# Master_Controller.net
KiCad netlist of a schematic drawn in Altium Designer
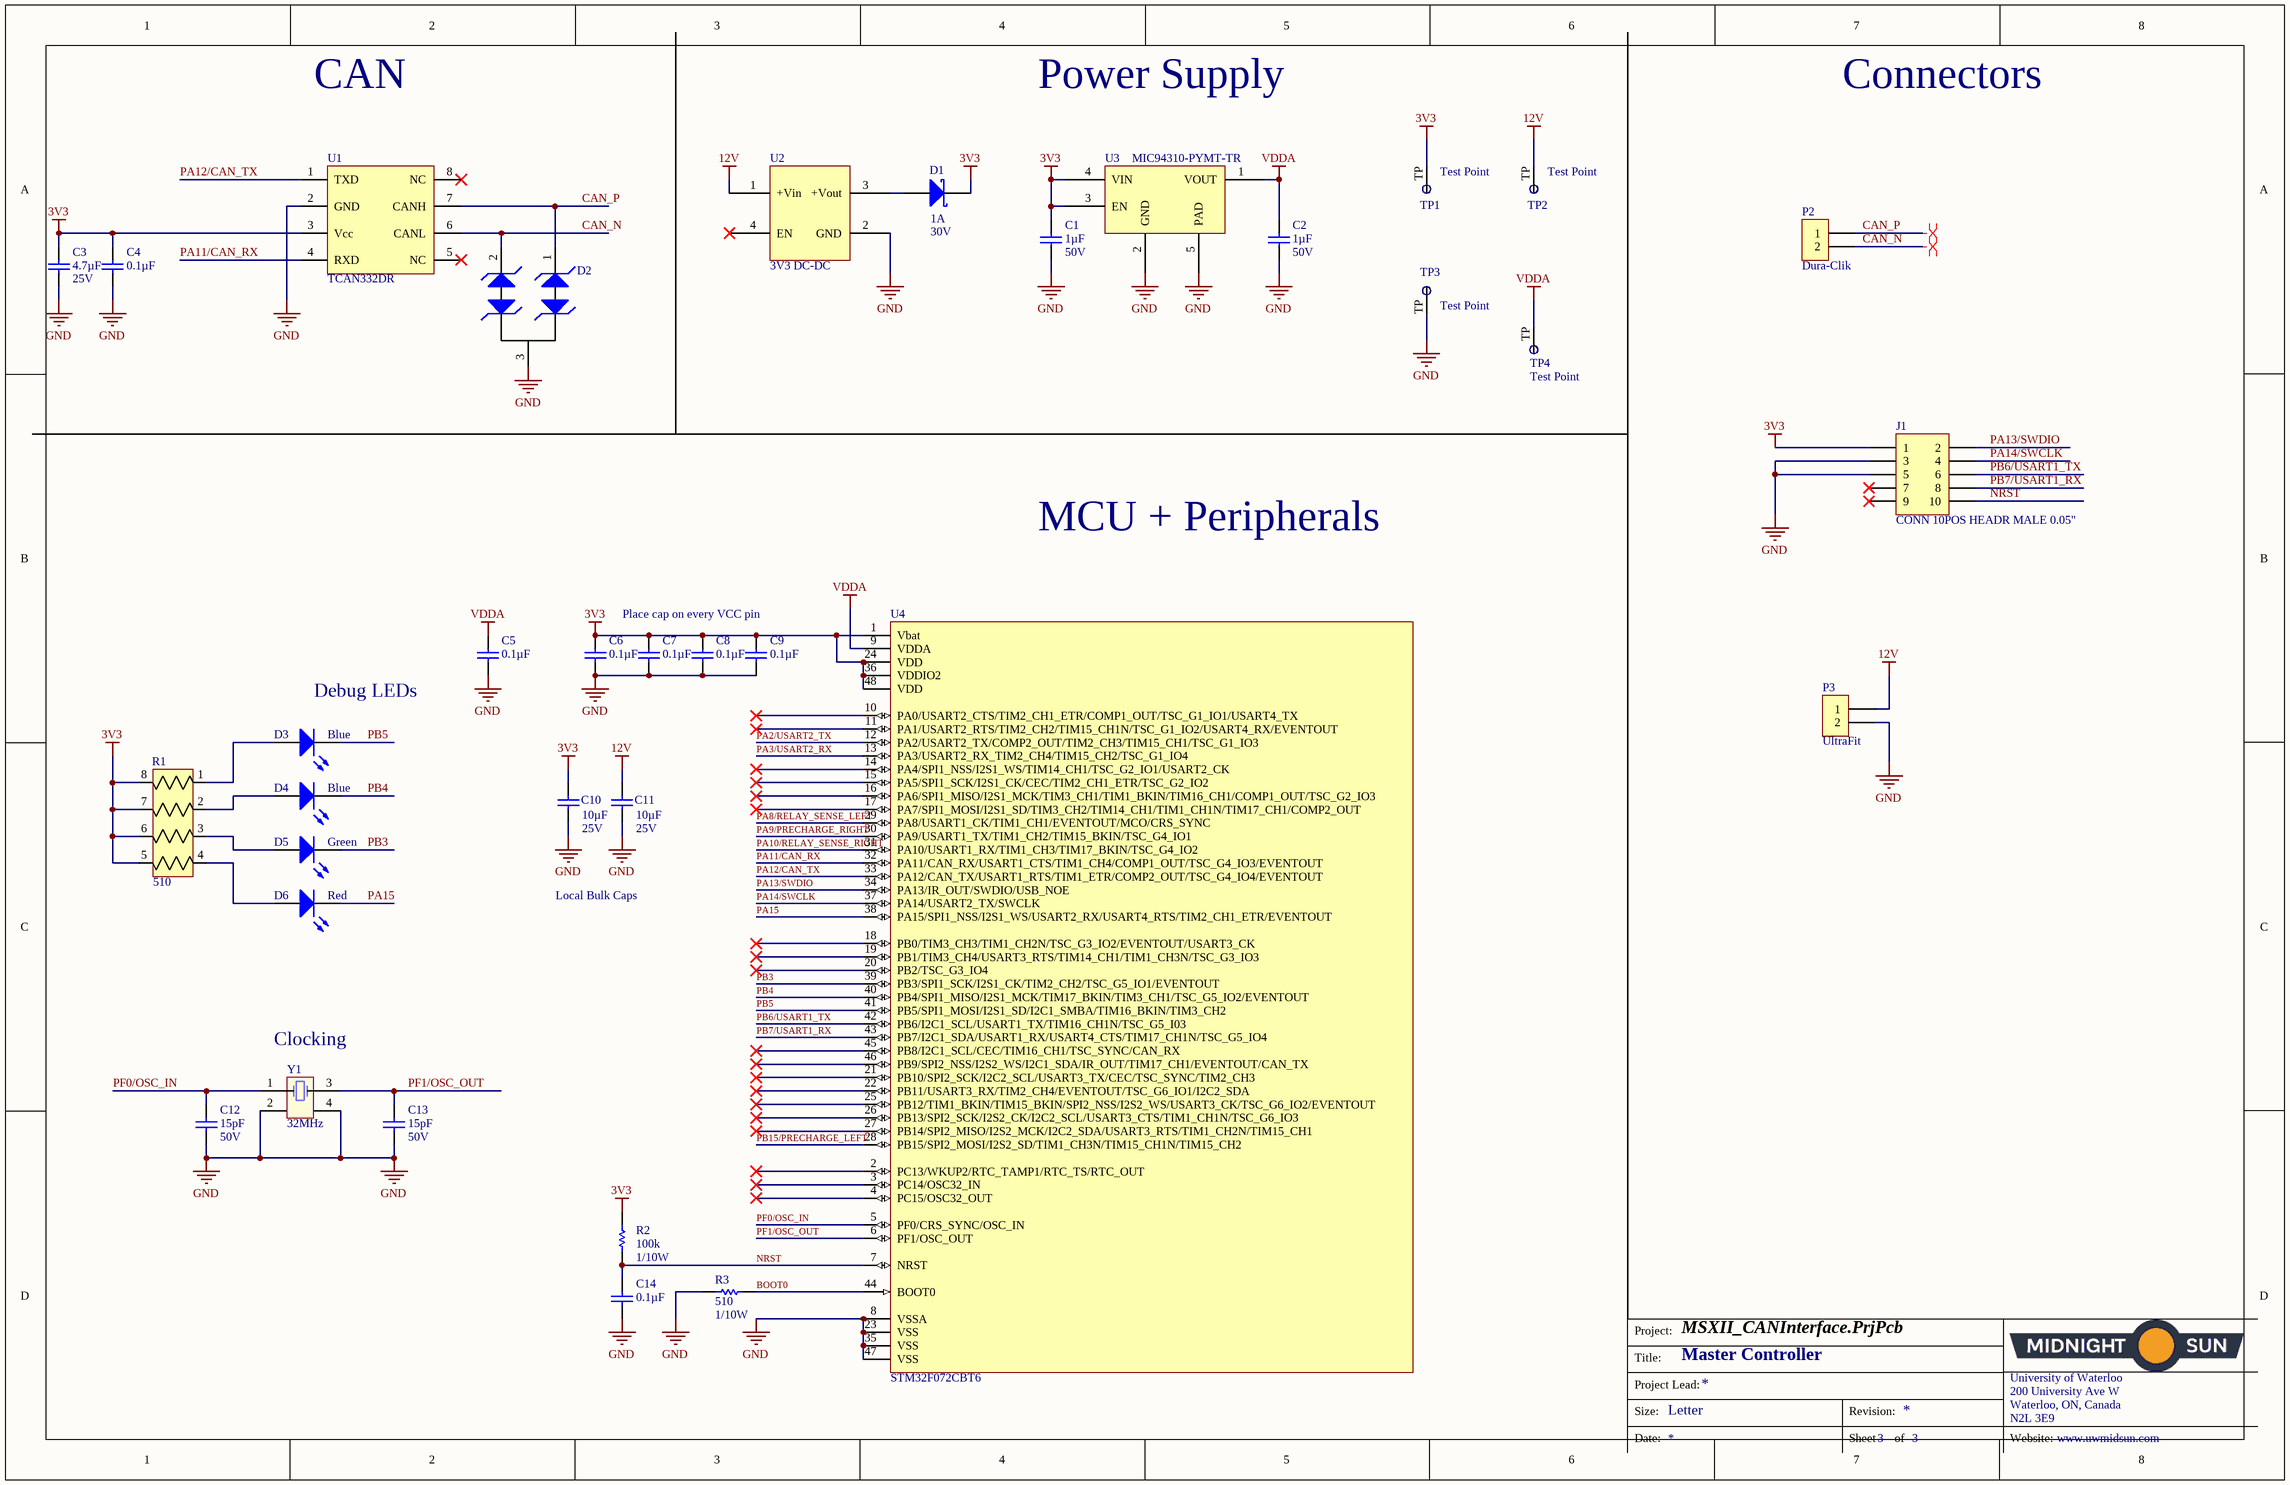
[diagram p0: Master_Controller.SchDoc]

(export (version "E")
  (design (tool "Eeschema 10.0.6"))
  (components
    (comp (ref "C1")
      (value "CAP CER 1UF 50V 10% X7R 0603")
      (footprint "CAP, 0603")
      (description "1µF ±10% 50V Ceramic Capacitor X7R 0603 (1608 Metric)")
      (fields
        (field (name "TOLERANCE") "±10%")
        (field (name "CAPACITANCE") "1µF")
        (field (name "VOLTAGE") "50V")
      )
      (libsource (lib "Schematic Diagrams") (part "CAP CER 1UF 50V 10% X7R 0603"))
    )
    (comp (ref "C2")
      (value "CAP CER 1UF 50V 10% X7R 0603")
      (footprint "CAP, 0603")
      (description "1µF ±10% 50V Ceramic Capacitor X7R 0603 (1608 Metric)")
      (fields
        (field (name "TOLERANCE") "±10%")
        (field (name "CAPACITANCE") "1µF")
        (field (name "VOLTAGE") "50V")
      )
      (libsource (lib "Schematic Diagrams") (part "CAP CER 1UF 50V 10% X7R 0603"))
    )
    (comp (ref "C3")
      (value "CAP CER 4.7UF 25V 10% X5R 0603")
      (footprint "CAP, 0603")
      (description "4.7µF ±10% 25V Ceramic Capacitor X5R 0603 (1608 Metric)")
      (fields
        (field (name "VOLTAGE") "25V")
        (field (name "TOLERANCE") "±10%")
        (field (name "CAPACITANCE") "4.7µF")
      )
      (libsource (lib "Schematic Diagrams") (part "CAP CER 4.7UF 25V 10% X5R 0603"))
    )
    (comp (ref "C4")
      (value "CAP CER 0.1UF 50V 10% X7R 0603")
      (footprint "CAP, 0603")
      (description "0.10µF ±10% 50V Ceramic Capacitor X7R 0603 (1608 Metric)")
      (fields
        (field (name "VOLTAGE") "50V")
        (field (name "TOLERANCE") "±10%")
        (field (name "CAPACITANCE") "0.1µF")
      )
      (libsource (lib "Schematic Diagrams") (part "CAP CER 0.1UF 50V 10% X7R 0603"))
    )
    (comp (ref "C5")
      (value "CAP CER 0.1UF 50V 10% X7R 0603")
      (footprint "CAP, 0603")
      (description "0.10µF ±10% 50V Ceramic Capacitor X7R 0603 (1608 Metric)")
      (fields
        (field (name "VOLTAGE") "50V")
        (field (name "TOLERANCE") "±10%")
        (field (name "CAPACITANCE") "0.1µF")
      )
      (libsource (lib "Schematic Diagrams") (part "CAP CER 0.1UF 50V 10% X7R 0603"))
    )
    (comp (ref "C6")
      (value "CAP CER 0.1UF 50V 10% X7R 0603")
      (footprint "CAP, 0603")
      (description "0.10µF ±10% 50V Ceramic Capacitor X7R 0603 (1608 Metric)")
      (fields
        (field (name "VOLTAGE") "50V")
        (field (name "TOLERANCE") "±10%")
        (field (name "CAPACITANCE") "0.1µF")
      )
      (libsource (lib "Schematic Diagrams") (part "CAP CER 0.1UF 50V 10% X7R 0603"))
    )
    (comp (ref "C7")
      (value "CAP CER 0.1UF 50V 10% X7R 0603")
      (footprint "CAP, 0603")
      (description "0.10µF ±10% 50V Ceramic Capacitor X7R 0603 (1608 Metric)")
      (fields
        (field (name "VOLTAGE") "50V")
        (field (name "TOLERANCE") "±10%")
        (field (name "CAPACITANCE") "0.1µF")
      )
      (libsource (lib "Schematic Diagrams") (part "CAP CER 0.1UF 50V 10% X7R 0603"))
    )
    (comp (ref "C8")
      (value "CAP CER 0.1UF 50V 10% X7R 0603")
      (footprint "CAP, 0603")
      (description "0.10µF ±10% 50V Ceramic Capacitor X7R 0603 (1608 Metric)")
      (fields
        (field (name "VOLTAGE") "50V")
        (field (name "TOLERANCE") "±10%")
        (field (name "CAPACITANCE") "0.1µF")
      )
      (libsource (lib "Schematic Diagrams") (part "CAP CER 0.1UF 50V 10% X7R 0603"))
    )
    (comp (ref "C9")
      (value "CAP CER 0.1UF 50V 10% X7R 0603")
      (footprint "CAP, 0603")
      (description "0.10µF ±10% 50V Ceramic Capacitor X7R 0603 (1608 Metric)")
      (fields
        (field (name "VOLTAGE") "50V")
        (field (name "TOLERANCE") "±10%")
        (field (name "CAPACITANCE") "0.1µF")
      )
      (libsource (lib "Schematic Diagrams") (part "CAP CER 0.1UF 50V 10% X7R 0603"))
    )
    (comp (ref "C10")
      (value "CAP CER 10uF 25V 10% X5R 0805")
      (footprint "CAP, 0805")
      (description "10µF ±10% 25V Ceramic Capacitor X5R 0805 (2012 Metric)")
      (fields
        (field (name "MANUFACTURER") "Murata Electronics North America")
        (field (name "MANUFACTURER PART NUMBER") "GRM21BR61E106KA73L")
        (field (name "VOLTAGE - RATED") "25V")
        (field (name "CAPACITANCE") "10µF")
      )
      (libsource (lib "Schematic Diagrams") (part "CAP CER 10uF 25V 10% X5R 0805"))
    )
    (comp (ref "C11")
      (value "CAP CER 10uF 25V 10% X5R 0805")
      (footprint "CAP, 0805")
      (description "10µF ±10% 25V Ceramic Capacitor X5R 0805 (2012 Metric)")
      (fields
        (field (name "MANUFACTURER") "Murata Electronics North America")
        (field (name "MANUFACTURER PART NUMBER") "GRM21BR61E106KA73L")
        (field (name "VOLTAGE - RATED") "25V")
        (field (name "CAPACITANCE") "10µF")
      )
      (libsource (lib "Schematic Diagrams") (part "CAP CER 10uF 25V 10% X5R 0805"))
    )
    (comp (ref "C12")
      (value "CAP CER 15PF 50V ±5% NPO 0603")
      (footprint "CAP, 0603")
      (description "15pF ±5% 50V Ceramic Capacitor C0G, NP0 0603 (1608 Metric)")
      (fields
        (field (name "VOLTAGE") "50V")
        (field (name "TOLERANCE") "±5%")
        (field (name "CAPACITANCE") "15pF")
      )
      (libsource (lib "Schematic Diagrams") (part "CAP CER 15PF 50V ±5% NPO 0603"))
    )
    (comp (ref "C13")
      (value "CAP CER 15PF 50V ±5% NPO 0603")
      (footprint "CAP, 0603")
      (description "15pF ±5% 50V Ceramic Capacitor C0G, NP0 0603 (1608 Metric)")
      (fields
        (field (name "VOLTAGE") "50V")
        (field (name "TOLERANCE") "±5%")
        (field (name "CAPACITANCE") "15pF")
      )
      (libsource (lib "Schematic Diagrams") (part "CAP CER 15PF 50V ±5% NPO 0603"))
    )
    (comp (ref "C14")
      (value "CAP CER 0.1UF 50V 10% X7R 0603")
      (footprint "CAP, 0603")
      (description "0.10µF ±10% 50V Ceramic Capacitor X7R 0603 (1608 Metric)")
      (fields
        (field (name "VOLTAGE") "50V")
        (field (name "TOLERANCE") "±10%")
        (field (name "CAPACITANCE") "0.1µF")
      )
      (libsource (lib "Schematic Diagrams") (part "CAP CER 0.1UF 50V 10% X7R 0603"))
    )
    (comp (ref "D1")
      (value "DIODE SCHOTTKY 30V 1A POWERDI123")
      (footprint "DIODE SCHOTTKY 30V 1A POWERDI123")
      (description "Diode Schottky 30V 1A Surface Mount PowerDI™ 123")
      (fields
        (field (name "MANUFACTURER") "Diodes Incorporated")
        (field (name "MANUFACTURER PART NUMBER") "DFLS130L-7")
        (field (name "CURRENT - AVERAGE RECTIFIED (IO)") "1A")
        (field (name "VOLTAGE - DC REVERSE (VR) (MAX)") "30V")
      )
      (libsource (lib "Schematic Diagrams") (part "DIODE SCHOTTKY 30V 1A POWERDI123"))
    )
    (comp (ref "D2")
      (value "DIODE TVS 24VWM 70VC SOT23")
      (footprint "SOT23")
      (description "TVS DIODE 24VWM 70VC SOT23")
      (libsource (lib "Schematic Diagrams") (part "DIODE TVS 24VWM 70VC SOT23"))
    )
    (comp (ref "D3")
      (value "LED BLUE CLEAR 2.8V 0603")
      (footprint "LED_0603")
      (description "Blue 470nm LED Indication - Discrete 2.8V 0603 (1608 Metric)")
      (fields (field (name "COLOR") "Blue"))
      (libsource (lib "Schematic Diagrams") (part "LED BLUE CLEAR 2.8V 0603"))
    )
    (comp (ref "D4")
      (value "LED BLUE CLEAR 2.8V 0603")
      (footprint "LED_0603")
      (description "Blue 470nm LED Indication - Discrete 2.8V 0603 (1608 Metric)")
      (fields (field (name "COLOR") "Blue"))
      (libsource (lib "Schematic Diagrams") (part "LED BLUE CLEAR 2.8V 0603"))
    )
    (comp (ref "D5")
      (value "LED GREEN CLEAR 2V 0603")
      (footprint "LED_0603")
      (description "Green 572nm LED Indication - Discrete 2V 0603 (1608 Metric)")
      (fields
        (field (name "COLOR") "Green")
        (field (name "MANUFACTURER") "Wurth Electronics Inc.")
        (field (name "MANUFACTURER PART NUMBER") "150060VS75000")
      )
      (libsource (lib "Schematic Diagrams") (part "LED GREEN CLEAR 2V 0603"))
    )
    (comp (ref "D6")
      (value "LED RED CLEAR 2V 0603")
      (footprint "LED_0603")
      (description "Red 631nm LED Indication - Discrete 2V 0603 (1608 Metric)")
      (fields
        (field (name "COLOR") "Red")
        (field (name "MANUFACTURER") "Wurth Electronics Inc.")
        (field (name "MANUFACTURER PART NUMBER") "150060RS75000")
      )
      (libsource (lib "Schematic Diagrams") (part "LED RED CLEAR 2V 0603"))
    )
    (comp (ref "J1")
      (value "CONN 10POS HEADR MALE 0.05\"")
      (footprint "CONN, 10POS 0.05\" Debug Header")
      (description "10 Positions Header Connector 0.050\" (1.27mm) Surface Mount Gold")
      (libsource (lib "Schematic Diagrams") (part "CONN 10POS HEADR MALE 0.05{dblquote}"))
    )
    (comp (ref "P2")
      (value "Dura-Clik")
      (footprint "CONN, 2POS Dura-Click Vertical")
      (description "2 Positions Header, Shrouded Connector 0.079\" (2.00mm) Surface Mount, Vertical Tin")
      (fields
        (field (name "MANUFACTURER") "Molex, LLC")
        (field (name "MANUFACTURER PART NUMBER") "5600200220")
      )
      (libsource (lib "Schematic Diagrams") (part "CONN 2POS DURA-CLIK 0.079{dblquote} VERT"))
    )
    (comp (ref "P3")
      (value "CONN 2POS ULTRA-FIT 0.138\"")
      (footprint "CONN, 2POS ULTRA-FIT")
      (description "2 Positions Header, Shrouded Connector 0.138\" (3.50mm) Through Hole Gold")
      (fields (field (name "VOLTAGE") "400V") (field (name "SERIES") "UltraFit"))
      (libsource (lib "Schematic Diagrams") (part "CONN 2POS ULTRA-FIT 0.138{dblquote}"))
    )
    (comp (ref "R1")
      (value "RES ARRAY 510 OHM 5% 4RES")
      (footprint "RES ARRAY 4 POS 0804")
      (description "RES ARRAY SMD 510 OHM 5% 4RES EXB-N8V511JX")
      (fields
        (field (name "MANUFACTURER") "Panasonic Electronic Components")
        (field (name "MANUFACTURER PART NUMBER") "EXB-N8V511JX")
        (field (name "RESISTANCE (OHMS)") "510")
      )
      (libsource (lib "Schematic Diagrams") (part "RES ARRAY 510 OHM 5% 4RES EXB-N8V511JX"))
    )
    (comp (ref "R2")
      (value "RES 100K OHM 5% 1/8W 0603")
      (footprint "RES, 0603")
      (description "RES SMD 100K OHM 5% 1/10W 0603")
      (fields
        (field (name "TOLERANCE") "±5%")
        (field (name "RESISTANCE") "100k")
        (field (name "POWER") "1/10W")
      )
      (libsource (lib "Schematic Diagrams") (part "RES 100K OHM 5% 1/8W 0603"))
    )
    (comp (ref "R3")
      (value "RES 510 OHM 5% 1/10W 0603")
      (footprint "RES, 0603")
      (description "RES SMD 510 OHM 5% 1/10W 0603")
      (fields
        (field (name "TOLERANCE") "±5%")
        (field (name "RESISTANCE") "510")
        (field (name "POWER") "1/10W")
      )
      (libsource (lib "Schematic Diagrams") (part "RES 510 OHM 5% 1/10W 0603"))
    )
    (comp (ref "TP1")
      (value "Test Point")
      (footprint "Test Point")
      (libsource (lib "Schematic Diagrams") (part "Test Point"))
    )
    (comp (ref "TP2")
      (value "Test Point")
      (footprint "Test Point")
      (libsource (lib "Schematic Diagrams") (part "Test Point"))
    )
    (comp (ref "TP3")
      (value "Test Point")
      (footprint "Test Point")
      (libsource (lib "Schematic Diagrams") (part "Test Point"))
    )
    (comp (ref "TP4")
      (value "Test Point")
      (footprint "Test Point")
      (libsource (lib "Schematic Diagrams") (part "Test Point"))
    )
    (comp (ref "U1")
      (value "IC CAN Tranceiver TCAN332DR")
      (footprint "TSOP65P280X145-8N")
      (description "1/1 Transceiver CAN 8-SOIC")
      (fields
        (field (name "MANUFACTURER PART NUMBER") "TCAN332DR")
        (field (name "DIGIKEY PART NUMBER") "296-43711-1-ND")
      )
      (libsource (lib "Schematic Diagrams") (part "IC CAN Tranceiver TCAN332DR"))
    )
    (comp (ref "U2")
      (value "IC DCDC 3.3V 0.5A 4-SMD")
      (footprint "IC DCDC 3.3V 0.5A 4-SMD")
      (description "Non-isolated PoL DC-DC Module 3.3V Output 0.5A 5-36V Input")
      (fields
        (field (name "MANUFACTURER") "Recom Power")
        (field (name "MANUFACTURER PART NUMBER") "ROF-78E3.3-0.5SMD-R")
      )
      (libsource (lib "Schematic Diagrams") (part "IC DCDC 3.3V 0.5A 4-SMD"))
    )
    (comp (ref "U3")
      (value "IC REG LDO 3V 0.2A 4-TDFN")
      (footprint "IC REG LDO 3V 0.2A 4-TDFN")
      (fields
        (field (name "MANUFACTURER") "Microchip Technology")
        (field (name "MANUFACTURER PART NUMBER") "MIC94310-PYMT-TR")
      )
      (libsource (lib "Schematic Diagrams") (part "IC REG LDO 3V 0.2A 4-TDFN"))
    )
    (comp (ref "U4")
      (value "IC MCU 32BIT 128KB FLASH 48LQFP")
      (footprint "TSQFP50P890X890X160-48M")
      (description "ARM® Cortex®-M0 STM32 F0 Microcontroller IC 32-Bit 48MHz 128KB (128K x 8) FLASH 48-LQFP (7x7)")
      (fields (field (name "MANUFACTURER PART NUMBER 1") "STM32F072CBT6"))
      (libsource (lib "Schematic Diagrams") (part "IC MCU 32BIT 128KB FLASH 48LQFP"))
    )
    (comp (ref "Y1")
      (value "CRYSTAL 32 MHz 8pF 4-SMD")
      (footprint "CX2520DB CRYSTAL")
      (description "32MHz ±15ppm Crystal 8pF 50 Ohm -40°C ~ 85°C AEC-Q200 Surface Mount 4-SMD, No Lead")
      (fields (field (name "FREQUENCY") "32MHz"))
      (libsource (lib "Schematic Diagrams") (part "CRYSTAL 32 MHz 8pF 4-SMD"))
    )
  )
  (nets
    (net (code "1") (name "/BOOT0") (class "Default")
      (node (ref "R3") (pin "2") (pinfunction "2_2") (pintype "passive"))
      (node (ref "U4") (pin "44") (pinfunction "BOOT0_44") (pintype "input"))
    )
    (net (code "2") (name "/CAN_N") (class "Default")
      (node (ref "D2") (pin "2") (pinfunction "Cathode2_2") (pintype "passive"))
      (node (ref "P2") (pin "2") (pinfunction "2_2") (pintype "passive"))
      (node (ref "U1") (pin "6") (pinfunction "CANL_6") (pintype "passive"))
    )
    (net (code "3") (name "/CAN_P") (class "Default")
      (node (ref "D2") (pin "1") (pinfunction "Cathode1_1") (pintype "passive"))
      (node (ref "P2") (pin "1") (pinfunction "1_1") (pintype "passive"))
      (node (ref "U1") (pin "7") (pinfunction "CANH_7") (pintype "passive"))
    )
    (net (code "4") (name "/NRST") (class "Default")
      (node (ref "C14") (pin "2") (pinfunction "2_2") (pintype "passive"))
      (node (ref "J1") (pin "10") (pinfunction "10_10") (pintype "passive"))
      (node (ref "R2") (pin "1") (pinfunction "1_1") (pintype "passive"))
      (node (ref "U4") (pin "7") (pinfunction "NRST_7") (pintype "bidirectional"))
    )
    (net (code "5") (name "/PA2{slash}USART2_TX") (class "Default")
      (node (ref "U4") (pin "12") (pinfunction "PA2/USART2_TX/COMP2_OUT/TIM2_CH3/TIM15_CH1/TSC_G1_IO3_12") (pintype "bidirectional"))
    )
    (net (code "6") (name "/PA3{slash}USART2_RX") (class "Default")
      (node (ref "U4") (pin "13") (pinfunction "PA3/USART2_RX_TIM2_CH4/TIM15_CH2/TSC_G1_IO4_13") (pintype "bidirectional"))
    )
    (net (code "7") (name "/PA8{slash}RELAY_SENSE_LEFT") (class "Default")
      (node (ref "U4") (pin "29") (pinfunction "PA8/USART1_CK/TIM1_CH1/EVENTOUT/MCO/CRS_SYNC_29") (pintype "bidirectional"))
    )
    (net (code "8") (name "/PA9{slash}PRECHARGE_RIGHT") (class "Default")
      (node (ref "U4") (pin "30") (pinfunction "PA9/USART1_TX/TIM1_CH2/TIM15_BKIN/TSC_G4_IO1_30") (pintype "bidirectional"))
    )
    (net (code "9") (name "/PA10{slash}RELAY_SENSE_RIGHT") (class "Default")
      (node (ref "U4") (pin "31") (pinfunction "PA10/USART1_RX/TIM1_CH3/TIM17_BKIN/TSC_G4_IO2_31") (pintype "bidirectional"))
    )
    (net (code "10") (name "/PA11{slash}CAN_RX") (class "Default")
      (node (ref "U1") (pin "4") (pinfunction "RXD_4") (pintype "passive"))
      (node (ref "U4") (pin "32") (pinfunction "PA11/CAN_RX/USART1_CTS/TIM1_CH4/COMP1_OUT/TSC_G4_IO3/EVENTOUT_32") (pintype "bidirectional"))
    )
    (net (code "11") (name "/PA12{slash}CAN_TX") (class "Default")
      (node (ref "U1") (pin "1") (pinfunction "TXD_1") (pintype "passive"))
      (node (ref "U4") (pin "33") (pinfunction "PA12/CAN_TX/USART1_RTS/TIM1_ETR/COMP2_OUT/TSC_G4_IO4/EVENTOUT_33") (pintype "bidirectional"))
    )
    (net (code "12") (name "/PA13{slash}SWDIO") (class "Default")
      (node (ref "J1") (pin "2") (pinfunction "2_2") (pintype "passive"))
      (node (ref "U4") (pin "34") (pinfunction "PA13/IR_OUT/SWDIO/USB_NOE_34") (pintype "bidirectional"))
    )
    (net (code "13") (name "/PA14{slash}SWCLK") (class "Default")
      (node (ref "J1") (pin "4") (pinfunction "4_4") (pintype "passive"))
      (node (ref "U4") (pin "37") (pinfunction "PA14/USART2_TX/SWCLK_37") (pintype "bidirectional"))
    )
    (net (code "14") (name "/PA15") (class "Default")
      (node (ref "D6") (pin "2") (pinfunction "K_2") (pintype "passive"))
      (node (ref "U4") (pin "38") (pinfunction "PA15/SPI1_NSS/I2S1_WS/USART2_RX/USART4_RTS/TIM2_CH1_ETR/EVENTOUT_38") (pintype "bidirectional"))
    )
    (net (code "15") (name "/PB3") (class "Default")
      (node (ref "D5") (pin "2") (pinfunction "K_2") (pintype "passive"))
      (node (ref "U4") (pin "39") (pinfunction "PB3/SPI1_SCK/I2S1_CK/TIM2_CH2/TSC_G5_IO1/EVENTOUT_39") (pintype "bidirectional"))
    )
    (net (code "16") (name "/PB4") (class "Default")
      (node (ref "D4") (pin "2") (pinfunction "K_2") (pintype "passive"))
      (node (ref "U4") (pin "40") (pinfunction "PB4/SPI1_MISO/I2S1_MCK/TIM17_BKIN/TIM3_CH1/TSC_G5_IO2/EVENTOUT_40") (pintype "bidirectional"))
    )
    (net (code "17") (name "/PB5") (class "Default")
      (node (ref "D3") (pin "2") (pinfunction "K_2") (pintype "passive"))
      (node (ref "U4") (pin "41") (pinfunction "PB5/SPI1_MOSI/I2S1_SD/I2C1_SMBA/TIM16_BKIN/TIM3_CH2_41") (pintype "bidirectional"))
    )
    (net (code "18") (name "/PB6{slash}USART1_TX") (class "Default")
      (node (ref "J1") (pin "6") (pinfunction "6_6") (pintype "passive"))
      (node (ref "U4") (pin "42") (pinfunction "PB6/I2C1_SCL/USART1_TX/TIM16_CH1N/TSC_G5_I03_42") (pintype "bidirectional"))
    )
    (net (code "19") (name "/PB7{slash}USART1_RX") (class "Default")
      (node (ref "J1") (pin "8") (pinfunction "8_8") (pintype "passive"))
      (node (ref "U4") (pin "43") (pinfunction "PB7/I2C1_SDA/USART1_RX/USART4_CTS/TIM17_CH1N/TSC_G5_IO4_43") (pintype "bidirectional"))
    )
    (net (code "20") (name "/PB15{slash}PRECHARGE_LEFT") (class "Default")
      (node (ref "U4") (pin "28") (pinfunction "PB15/SPI2_MOSI/I2S2_SD/TIM1_CH3N/TIM15_CH1N/TIM15_CH2_28") (pintype "bidirectional"))
    )
    (net (code "21") (name "/PF0{slash}OSC_IN") (class "Default")
      (node (ref "C12") (pin "2") (pinfunction "2_2") (pintype "passive"))
      (node (ref "U4") (pin "5") (pinfunction "PF0/CRS_SYNC/OSC_IN_5") (pintype "bidirectional"))
      (node (ref "Y1") (pin "1") (pinfunction "OSC1_1") (pintype "passive"))
    )
    (net (code "22") (name "/PF1{slash}OSC_OUT") (class "Default")
      (node (ref "C13") (pin "2") (pinfunction "2_2") (pintype "passive"))
      (node (ref "U4") (pin "6") (pinfunction "PF1/OSC_OUT_6") (pintype "bidirectional"))
      (node (ref "Y1") (pin "3") (pinfunction "OSC2_3") (pintype "passive"))
    )
    (net (code "23") (name "3V3") (class "Default")
      (node (ref "C1") (pin "1") (pinfunction "1_1") (pintype "passive"))
      (node (ref "C10") (pin "1") (pinfunction "1_1") (pintype "passive"))
      (node (ref "C3") (pin "2") (pinfunction "2_2") (pintype "passive"))
      (node (ref "C4") (pin "2") (pinfunction "2_2") (pintype "passive"))
      (node (ref "C6") (pin "2") (pinfunction "2_2") (pintype "passive"))
      (node (ref "C7") (pin "2") (pinfunction "2_2") (pintype "passive"))
      (node (ref "C8") (pin "2") (pinfunction "2_2") (pintype "passive"))
      (node (ref "C9") (pin "2") (pinfunction "2_2") (pintype "passive"))
      (node (ref "D1") (pin "2") (pinfunction "K_2") (pintype "passive"))
      (node (ref "J1") (pin "1") (pinfunction "1_1") (pintype "passive"))
      (node (ref "R1") (pin "5") (pinfunction "5_5") (pintype "passive"))
      (node (ref "R1") (pin "6") (pinfunction "6_6") (pintype "passive"))
      (node (ref "R1") (pin "7") (pinfunction "7_7") (pintype "passive"))
      (node (ref "R1") (pin "8") (pinfunction "8_8") (pintype "passive"))
      (node (ref "R2") (pin "2") (pinfunction "2_2") (pintype "passive"))
      (node (ref "TP1") (pin "TP") (pinfunction "1_TP") (pintype "passive"))
      (node (ref "U1") (pin "3") (pinfunction "Vcc_3") (pintype "passive"))
      (node (ref "U3") (pin "3") (pinfunction "EN_3") (pintype "passive"))
      (node (ref "U3") (pin "4") (pinfunction "VIN_4") (pintype "passive"))
      (node (ref "U4") (pin "1") (pinfunction "Vbat_1") (pintype "power_in"))
      (node (ref "U4") (pin "24") (pinfunction "VDD_24") (pintype "power_in"))
      (node (ref "U4") (pin "36") (pinfunction "VDDIO2_36") (pintype "power_in"))
      (node (ref "U4") (pin "48") (pinfunction "VDD_48") (pintype "power_in"))
    )
    (net (code "24") (name "12V") (class "Default")
      (node (ref "C11") (pin "1") (pinfunction "1_1") (pintype "passive"))
      (node (ref "P3") (pin "1") (pinfunction "1_1") (pintype "passive"))
      (node (ref "TP2") (pin "TP") (pinfunction "1_TP") (pintype "passive"))
      (node (ref "U2") (pin "1") (pinfunction "+Vin_1") (pintype "passive"))
    )
    (net (code "25") (name "GND") (class "Default")
      (node (ref "C1") (pin "2") (pinfunction "2_2") (pintype "passive"))
      (node (ref "C10") (pin "2") (pinfunction "2_2") (pintype "passive"))
      (node (ref "C11") (pin "2") (pinfunction "2_2") (pintype "passive"))
      (node (ref "C12") (pin "1") (pinfunction "1_1") (pintype "passive"))
      (node (ref "C13") (pin "1") (pinfunction "1_1") (pintype "passive"))
      (node (ref "C14") (pin "1") (pinfunction "1_1") (pintype "passive"))
      (node (ref "C2") (pin "2") (pinfunction "2_2") (pintype "passive"))
      (node (ref "C3") (pin "1") (pinfunction "1_1") (pintype "passive"))
      (node (ref "C4") (pin "1") (pinfunction "1_1") (pintype "passive"))
      (node (ref "C5") (pin "1") (pinfunction "1_1") (pintype "passive"))
      (node (ref "C6") (pin "1") (pinfunction "1_1") (pintype "passive"))
      (node (ref "C7") (pin "1") (pinfunction "1_1") (pintype "passive"))
      (node (ref "C8") (pin "1") (pinfunction "1_1") (pintype "passive"))
      (node (ref "C9") (pin "1") (pinfunction "1_1") (pintype "passive"))
      (node (ref "D2") (pin "3") (pinfunction "Common_Cathode_3") (pintype "power_in"))
      (node (ref "J1") (pin "3") (pinfunction "3_3") (pintype "passive"))
      (node (ref "J1") (pin "5") (pinfunction "5_5") (pintype "passive"))
      (node (ref "P3") (pin "2") (pinfunction "2_2") (pintype "passive"))
      (node (ref "R3") (pin "1") (pinfunction "1_1") (pintype "passive"))
      (node (ref "TP3") (pin "TP") (pinfunction "1_TP") (pintype "passive"))
      (node (ref "U1") (pin "2") (pinfunction "GND_2") (pintype "passive"))
      (node (ref "U2") (pin "2") (pinfunction "GND_2") (pintype "passive"))
      (node (ref "U3") (pin "2") (pinfunction "GND_2") (pintype "passive"))
      (node (ref "U3") (pin "5") (pinfunction "PAD_5") (pintype "passive"))
      (node (ref "U4") (pin "23") (pinfunction "VSS_23") (pintype "power_in"))
      (node (ref "U4") (pin "35") (pinfunction "VSS_35") (pintype "power_in"))
      (node (ref "U4") (pin "47") (pinfunction "VSS_47") (pintype "power_in"))
      (node (ref "U4") (pin "8") (pinfunction "VSSA_8") (pintype "power_in"))
      (node (ref "Y1") (pin "2") (pinfunction "2_2") (pintype "passive"))
      (node (ref "Y1") (pin "4") (pinfunction "3_4") (pintype "passive"))
    )
    (net (code "26") (name "Net-(D1-A)") (class "Default")
      (node (ref "D1") (pin "1") (pinfunction "A_1") (pintype "passive"))
      (node (ref "U2") (pin "3") (pinfunction "+Vout_3") (pintype "passive"))
    )
    (net (code "27") (name "Net-(D3-A)") (class "Default")
      (node (ref "D3") (pin "1") (pinfunction "A_1") (pintype "passive"))
      (node (ref "R1") (pin "1") (pinfunction "1_1") (pintype "passive"))
    )
    (net (code "28") (name "Net-(D4-A)") (class "Default")
      (node (ref "D4") (pin "1") (pinfunction "A_1") (pintype "passive"))
      (node (ref "R1") (pin "2") (pinfunction "2_2") (pintype "passive"))
    )
    (net (code "29") (name "Net-(D5-A)") (class "Default")
      (node (ref "D5") (pin "1") (pinfunction "A_1") (pintype "passive"))
      (node (ref "R1") (pin "3") (pinfunction "3_3") (pintype "passive"))
    )
    (net (code "30") (name "Net-(D6-A)") (class "Default")
      (node (ref "D6") (pin "1") (pinfunction "A_1") (pintype "passive"))
      (node (ref "R1") (pin "4") (pinfunction "4_4") (pintype "passive"))
    )
    (net (code "31") (name "VDDA") (class "Default")
      (node (ref "C2") (pin "1") (pinfunction "1_1") (pintype "passive"))
      (node (ref "C5") (pin "2") (pinfunction "2_2") (pintype "passive"))
      (node (ref "TP4") (pin "TP") (pinfunction "1_TP") (pintype "passive"))
      (node (ref "U3") (pin "1") (pinfunction "VOUT_1") (pintype "passive"))
      (node (ref "U4") (pin "9") (pinfunction "VDDA_9") (pintype "power_in"))
    )
    (net (code "32") (name "unconnected-(J1-Pad7)") (class "Default")
      (node (ref "J1") (pin "7") (pinfunction "7_7") (pintype "passive+no_connect"))
    )
    (net (code "33") (name "unconnected-(J1-Pad9)") (class "Default")
      (node (ref "J1") (pin "9") (pinfunction "9_9") (pintype "passive+no_connect"))
    )
    (net (code "34") (name "unconnected-(U1-NC-Pad5)") (class "Default")
      (node (ref "U1") (pin "5") (pinfunction "NC_5") (pintype "passive+no_connect"))
    )
    (net (code "35") (name "unconnected-(U1-NC-Pad8)") (class "Default")
      (node (ref "U1") (pin "8") (pinfunction "NC_8") (pintype "passive+no_connect"))
    )
    (net (code "36") (name "unconnected-(U2-EN-Pad4)") (class "Default")
      (node (ref "U2") (pin "4") (pinfunction "EN_4") (pintype "passive+no_connect"))
    )
    (net (code "37") (name "unconnected-(U4-PA0{slash}USART2_CTS{slash}TIM2_CH1_ETR{slash}COMP1_OUT{slash}TSC_G1_IO1{slash}USART4_TX-Pad10)") (class "Default")
      (node (ref "U4") (pin "10") (pinfunction "PA0/USART2_CTS/TIM2_CH1_ETR/COMP1_OUT/TSC_G1_IO1/USART4_TX_10") (pintype "bidirectional+no_connect"))
    )
    (net (code "38") (name "unconnected-(U4-PA1{slash}USART2_RTS{slash}TIM2_CH2{slash}TIM15_CH1N{slash}TSC_G1_IO2{slash}USART4_RX{slash}EVENTOUT-Pad11)") (class "Default")
      (node (ref "U4") (pin "11") (pinfunction "PA1/USART2_RTS/TIM2_CH2/TIM15_CH1N/TSC_G1_IO2/USART4_RX/EVENTOUT_11") (pintype "bidirectional+no_connect"))
    )
    (net (code "39") (name "unconnected-(U4-PA4{slash}SPI1_NSS{slash}I2S1_WS{slash}TIM14_CH1{slash}TSC_G2_IO1{slash}USART2_CK-Pad14)") (class "Default")
      (node (ref "U4") (pin "14") (pinfunction "PA4/SPI1_NSS/I2S1_WS/TIM14_CH1/TSC_G2_IO1/USART2_CK_14") (pintype "bidirectional+no_connect"))
    )
    (net (code "40") (name "unconnected-(U4-PA5{slash}SPI1_SCK{slash}I2S1_CK{slash}CEC{slash}TIM2_CH1_ETR{slash}TSC_G2_IO2-Pad15)") (class "Default")
      (node (ref "U4") (pin "15") (pinfunction "PA5/SPI1_SCK/I2S1_CK/CEC/TIM2_CH1_ETR/TSC_G2_IO2_15") (pintype "bidirectional+no_connect"))
    )
    (net (code "41") (name "unconnected-(U4-PA6{slash}SPI1_MISO{slash}I2S1_MCK{slash}TIM3_CH1{slash}TIM1_BKIN{slash}TIM16_CH1{slash}COMP1_OUT{slash}TSC_G2_IO3-Pad16)") (class "Default")
      (node (ref "U4") (pin "16") (pinfunction "PA6/SPI1_MISO/I2S1_MCK/TIM3_CH1/TIM1_BKIN/TIM16_CH1/COMP1_OUT/TSC_G2_IO3_16") (pintype "bidirectional+no_connect"))
    )
    (net (code "42") (name "unconnected-(U4-PA7{slash}SPI1_MOSI{slash}I2S1_SD{slash}TIM3_CH2{slash}TIM14_CH1{slash}TIM1_CH1N{slash}TIM17_CH1{slash}COMP2_OUT-Pad17)") (class "Default")
      (node (ref "U4") (pin "17") (pinfunction "PA7/SPI1_MOSI/I2S1_SD/TIM3_CH2/TIM14_CH1/TIM1_CH1N/TIM17_CH1/COMP2_OUT_17") (pintype "bidirectional+no_connect"))
    )
    (net (code "43") (name "unconnected-(U4-PB0{slash}TIM3_CH3{slash}TIM1_CH2N{slash}TSC_G3_IO2{slash}EVENTOUT{slash}USART3_CK-Pad18)") (class "Default")
      (node (ref "U4") (pin "18") (pinfunction "PB0/TIM3_CH3/TIM1_CH2N/TSC_G3_IO2/EVENTOUT/USART3_CK_18") (pintype "bidirectional+no_connect"))
    )
    (net (code "44") (name "unconnected-(U4-PB1{slash}TIM3_CH4{slash}USART3_RTS{slash}TIM14_CH1{slash}TIM1_CH3N{slash}TSC_G3_IO3-Pad19)") (class "Default")
      (node (ref "U4") (pin "19") (pinfunction "PB1/TIM3_CH4/USART3_RTS/TIM14_CH1/TIM1_CH3N/TSC_G3_IO3_19") (pintype "bidirectional+no_connect"))
    )
    (net (code "45") (name "unconnected-(U4-PB2{slash}TSC_G3_IO4-Pad20)") (class "Default")
      (node (ref "U4") (pin "20") (pinfunction "PB2/TSC_G3_IO4_20") (pintype "bidirectional+no_connect"))
    )
    (net (code "46") (name "unconnected-(U4-PB8{slash}I2C1_SCL{slash}CEC{slash}TIM16_CH1{slash}TSC_SYNC{slash}CAN_RX-Pad45)") (class "Default")
      (node (ref "U4") (pin "45") (pinfunction "PB8/I2C1_SCL/CEC/TIM16_CH1/TSC_SYNC/CAN_RX_45") (pintype "bidirectional+no_connect"))
    )
    (net (code "47") (name "unconnected-(U4-PB9{slash}SPI2_NSS{slash}I2S2_WS{slash}I2C1_SDA{slash}IR_OUT{slash}TIM17_CH1{slash}EVENTOUT{slash}CAN_TX-Pad46)") (class "Default")
      (node (ref "U4") (pin "46") (pinfunction "PB9/SPI2_NSS/I2S2_WS/I2C1_SDA/IR_OUT/TIM17_CH1/EVENTOUT/CAN_TX_46") (pintype "bidirectional+no_connect"))
    )
    (net (code "48") (name "unconnected-(U4-PB10{slash}SPI2_SCK{slash}I2C2_SCL{slash}USART3_TX{slash}CEC{slash}TSC_SYNC{slash}TIM2_CH3-Pad21)") (class "Default")
      (node (ref "U4") (pin "21") (pinfunction "PB10/SPI2_SCK/I2C2_SCL/USART3_TX/CEC/TSC_SYNC/TIM2_CH3_21") (pintype "bidirectional+no_connect"))
    )
    (net (code "49") (name "unconnected-(U4-PB11{slash}USART3_RX{slash}TIM2_CH4{slash}EVENTOUT{slash}TSC_G6_IO1{slash}I2C2_SDA-Pad22)") (class "Default")
      (node (ref "U4") (pin "22") (pinfunction "PB11/USART3_RX/TIM2_CH4/EVENTOUT/TSC_G6_IO1/I2C2_SDA_22") (pintype "bidirectional+no_connect"))
    )
    (net (code "50") (name "unconnected-(U4-PB12{slash}TIM1_BKIN{slash}TIM15_BKIN{slash}SPI2_NSS{slash}I2S2_WS{slash}USART3_CK{slash}TSC_G6_IO2{slash}EVENTOUT-Pad25)") (class "Default")
      (node (ref "U4") (pin "25") (pinfunction "PB12/TIM1_BKIN/TIM15_BKIN/SPI2_NSS/I2S2_WS/USART3_CK/TSC_G6_IO2/EVENTOUT_25") (pintype "bidirectional+no_connect"))
    )
    (net (code "51") (name "unconnected-(U4-PB13{slash}SPI2_SCK{slash}I2S2_CK{slash}I2C2_SCL{slash}USART3_CTS{slash}TIM1_CH1N{slash}TSC_G6_IO3-Pad26)") (class "Default")
      (node (ref "U4") (pin "26") (pinfunction "PB13/SPI2_SCK/I2S2_CK/I2C2_SCL/USART3_CTS/TIM1_CH1N/TSC_G6_IO3_26") (pintype "bidirectional+no_connect"))
    )
    (net (code "52") (name "unconnected-(U4-PB14{slash}SPI2_MISO{slash}I2S2_MCK{slash}I2C2_SDA{slash}USART3_RTS{slash}TIM1_CH2N{slash}TIM15_CH1-Pad27)") (class "Default")
      (node (ref "U4") (pin "27") (pinfunction "PB14/SPI2_MISO/I2S2_MCK/I2C2_SDA/USART3_RTS/TIM1_CH2N/TIM15_CH1_27") (pintype "bidirectional+no_connect"))
    )
    (net (code "53") (name "unconnected-(U4-PC13{slash}WKUP2{slash}RTC_TAMP1{slash}RTC_TS{slash}RTC_OUT-Pad2)") (class "Default")
      (node (ref "U4") (pin "2") (pinfunction "PC13/WKUP2/RTC_TAMP1/RTC_TS/RTC_OUT_2") (pintype "bidirectional+no_connect"))
    )
    (net (code "54") (name "unconnected-(U4-PC14{slash}OSC32_IN-Pad3)") (class "Default")
      (node (ref "U4") (pin "3") (pinfunction "PC14/OSC32_IN_3") (pintype "bidirectional+no_connect"))
    )
    (net (code "55") (name "unconnected-(U4-PC15{slash}OSC32_OUT-Pad4)") (class "Default")
      (node (ref "U4") (pin "4") (pinfunction "PC15/OSC32_OUT_4") (pintype "bidirectional+no_connect"))
    )
  )
)
